# PWR.net
KiCad netlist of a schematic drawn in Altium Designer
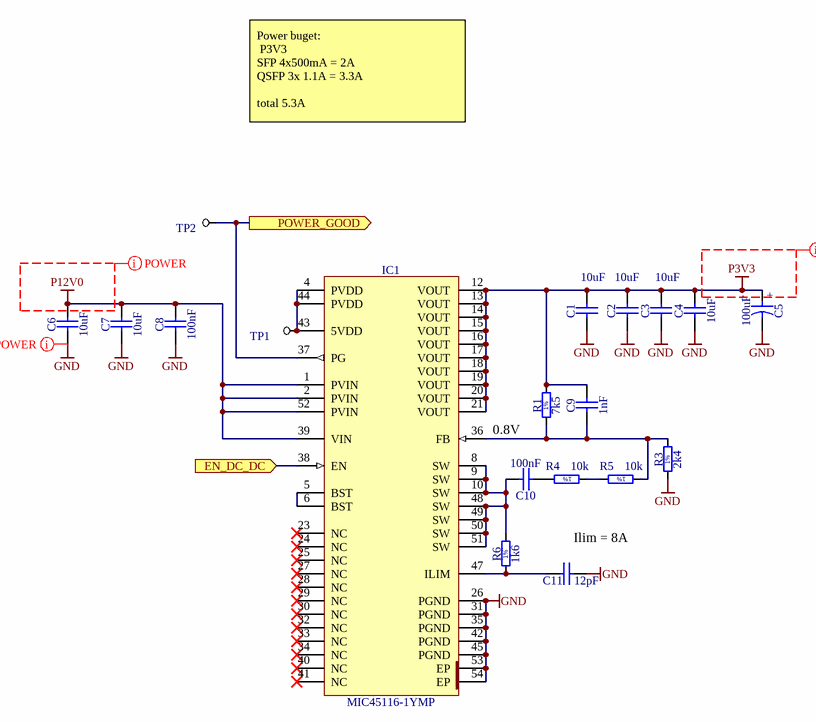
[diagram p0: PWR.SchDoc]

(export (version "E")
  (design (tool "Eeschema 10.0.6"))
  (components
    (comp (ref "C1")
      (value "10uF")
      (footprint "CAPC2012X135N")
      (description "Non-polarised capacitor")
      (fields
        (field (name "PART NUMBER") "CC0805_10UF_10V_10%_X7R")
        (field (name "VOLTAGE") "10V")
        (field (name "AUTHOR") "CERN DEM JLC")
      )
      (libsource (lib "Capacitors") (part "Capacitor - non polarized"))
    )
    (comp (ref "C2")
      (value "10uF")
      (footprint "CAPC2012X135N")
      (description "Non-polarised capacitor")
      (fields
        (field (name "PART NUMBER") "CC0805_10UF_10V_10%_X7R")
        (field (name "VOLTAGE") "10V")
        (field (name "AUTHOR") "CERN DEM JLC")
      )
      (libsource (lib "Capacitors") (part "Capacitor - non polarized"))
    )
    (comp (ref "C3")
      (value "10uF")
      (footprint "CAPC2012X135N")
      (description "Non-polarised capacitor")
      (fields
        (field (name "PART NUMBER") "CC0805_10UF_10V_10%_X7R")
        (field (name "VOLTAGE") "10V")
        (field (name "AUTHOR") "CERN DEM JLC")
      )
      (libsource (lib "Capacitors") (part "Capacitor - non polarized"))
    )
    (comp (ref "C4")
      (value "10uF")
      (footprint "CAPC2012X135N")
      (description "Non-polarised capacitor")
      (fields
        (field (name "PART NUMBER") "CC0805_10UF_10V_10%_X7R")
        (field (name "VOLTAGE") "10V")
        (field (name "AUTHOR") "CERN DEM JLC")
      )
      (libsource (lib "Capacitors") (part "Capacitor - non polarized"))
    )
    (comp (ref "C5")
      (value "100uF")
      (footprint "CAPAE660X540N")
      (description "Polarised capacitor")
      (fields
        (field (name "PART NUMBER") "CAE660-540_100UF_16V_20%")
        (field (name "VOLTAGE") "16V")
        (field (name "AUTHOR") "CERN DEM JLC")
      )
      (libsource (lib "Capacitors") (part "Capacitor - polarized"))
    )
    (comp (ref "C6")
      (value "10uF")
      (footprint "CAPC3216X140N")
      (description "Non-polarised capacitor")
      (fields
        (field (name "PART NUMBER") "CC1206_10UF_16V_10%_X7R")
        (field (name "VOLTAGE") "16V")
        (field (name "AUTHOR") "CERN DEM JLC")
      )
      (libsource (lib "Capacitors") (part "Capacitor - non polarized"))
    )
    (comp (ref "C7")
      (value "10uF")
      (footprint "CAPC3216X140N")
      (description "Non-polarised capacitor")
      (fields
        (field (name "PART NUMBER") "CC1206_10UF_16V_10%_X7R")
        (field (name "VOLTAGE") "16V")
        (field (name "AUTHOR") "CERN DEM JLC")
      )
      (libsource (lib "Capacitors") (part "Capacitor - non polarized"))
    )
    (comp (ref "C8")
      (value "100nF")
      (footprint "CAPC1005X55N")
      (description "Non-polarised capacitor")
      (fields
        (field (name "PART NUMBER") "CC0402_100NF_16V_10%_X5R")
        (field (name "VOLTAGE") "16V")
        (field (name "AUTHOR") "CERN DEM JLC")
      )
      (libsource (lib "Capacitors") (part "Capacitor - non polarized"))
    )
    (comp (ref "C9")
      (value "1nF")
      (footprint "CAPC1005X55N")
      (description "Non-polarised capacitor")
      (fields
        (field (name "PART NUMBER") "CC0402_1NF_50V_10%_X7R")
        (field (name "VOLTAGE") "50V")
        (field (name "AUTHOR") "CERN DEM JLC")
      )
      (libsource (lib "Capacitors") (part "Capacitor - non polarized"))
    )
    (comp (ref "C10")
      (value "100nF")
      (footprint "CAPC1005X55N")
      (description "Non-polarised capacitor")
      (fields
        (field (name "PART NUMBER") "CC0402_100NF_16V_10%_X5R")
        (field (name "VOLTAGE") "16V")
        (field (name "AUTHOR") "CERN DEM JLC")
      )
      (libsource (lib "Capacitors") (part "Capacitor - non polarized"))
    )
    (comp (ref "C11")
      (value "12pF")
      (footprint "CAPC1005X55N")
      (description "Non-polarised capacitor")
      (fields
        (field (name "PART NUMBER") "CC0402_12PF_50V_5%_C0G")
        (field (name "VOLTAGE") "50V")
        (field (name "AUTHOR") "CERN DEM JLC")
      )
      (libsource (lib "Capacitors") (part "Capacitor - non polarized"))
    )
    (comp (ref "IC1")
      (value "MIC45116-1YMP")
      (footprint "MICROCHIP_H3QFN88-52LD-PL-3")
      (description "0.8V to 85% PVIN (4.75-19V), 6A Synchronous Step-Down Regulator Module")
      (fields (field (name "MANUFACTURER") "MICROCHIP TECHNOLOGY") (field (name "AUTHOR") "CERN DEM JMW"))
      (libsource (lib "ICs And Semiconductors") (part "MIC45116"))
    )
    (comp (ref "R1")
      (value "7k5")
      (footprint "RESC1005X40N")
      (description "Resistor - 1%")
      (fields
        (field (name "PART NUMBER") "R0402_7K5_1%_0.0625W_100PPM")
        (field (name "POWER") "0.0625W")
        (field (name "AUTHOR") "CERN DEM JLC")
      )
      (libsource (lib "Resistors") (part "Resistor - 1%"))
    )
    (comp (ref "R3")
      (value "2k4")
      (footprint "RESC1005X40N")
      (description "Resistor - 1%")
      (fields
        (field (name "PART NUMBER") "R0402_2K4_1%_0.0625W_100PPM")
        (field (name "POWER") "0.0625W")
        (field (name "AUTHOR") "CERN DEM JLC")
      )
      (libsource (lib "Resistors") (part "Resistor - 1%"))
    )
    (comp (ref "R4")
      (value "10k")
      (footprint "RESC1005X40N")
      (description "Resistor - 1%")
      (fields
        (field (name "PART NUMBER") "R0402_10K_1%_0.0625W_100PPM")
        (field (name "POWER") "0.0625W")
        (field (name "AUTHOR") "CERN DEM JLC")
      )
      (libsource (lib "Resistors") (part "Resistor - 1%"))
    )
    (comp (ref "R5")
      (value "10k")
      (footprint "RESC1005X40N")
      (description "Resistor - 1%")
      (fields
        (field (name "PART NUMBER") "R0402_10K_1%_0.0625W_100PPM")
        (field (name "POWER") "0.0625W")
        (field (name "AUTHOR") "CERN DEM JLC")
      )
      (libsource (lib "Resistors") (part "Resistor - 1%"))
    )
    (comp (ref "R6")
      (value "1k6")
      (footprint "RESC1005X40N")
      (description "Resistor - 1%")
      (fields
        (field (name "PART NUMBER") "R0402_1K6_1%_0.0625W_100PPM")
        (field (name "POWER") "0.0625W")
        (field (name "AUTHOR") "CERN DEM JLC")
      )
      (libsource (lib "Resistors") (part "Resistor - 1%"))
    )
    (comp (ref "TP1")
      (value "TP")
      (footprint "TP")
      (description "Testpoint")
      (libsource (lib "LIBRARY_SCH") (part "TP"))
    )
    (comp (ref "TP2")
      (value "TP")
      (footprint "TP")
      (description "Testpoint")
      (libsource (lib "LIBRARY_SCH") (part "TP"))
    )
  )
  (nets
    (net (code "1") (name "/EN_DC_DC") (class "Default")
      (node (ref "IC1") (pin "38") (pinfunction "EN_38") (pintype "input"))
    )
    (net (code "2") (name "/POWER_GOOD") (class "Default")
      (node (ref "IC1") (pin "37") (pinfunction "PG_37") (pintype "output"))
      (node (ref "TP2") (pin "1") (pintype "passive"))
    )
    (net (code "3") (name "GND") (class "Default")
      (node (ref "C1") (pin "1") (pinfunction "1_1") (pintype "passive"))
      (node (ref "C11") (pin "1") (pinfunction "1_1") (pintype "passive"))
      (node (ref "C2") (pin "1") (pinfunction "1_1") (pintype "passive"))
      (node (ref "C3") (pin "1") (pinfunction "1_1") (pintype "passive"))
      (node (ref "C4") (pin "1") (pinfunction "1_1") (pintype "passive"))
      (node (ref "C5") (pin "2") (pinfunction "2_2") (pintype "passive"))
      (node (ref "C6") (pin "1") (pinfunction "1_1") (pintype "passive"))
      (node (ref "C7") (pin "1") (pinfunction "1_1") (pintype "passive"))
      (node (ref "C8") (pin "1") (pinfunction "1_1") (pintype "passive"))
      (node (ref "IC1") (pin "26") (pinfunction "PGND_26") (pintype "power_in"))
      (node (ref "IC1") (pin "31") (pinfunction "PGND_31") (pintype "power_in"))
      (node (ref "IC1") (pin "35") (pinfunction "PGND_35") (pintype "power_in"))
      (node (ref "IC1") (pin "42") (pinfunction "PGND_42") (pintype "power_in"))
      (node (ref "IC1") (pin "45") (pinfunction "PGND_45") (pintype "power_in"))
      (node (ref "IC1") (pin "53") (pinfunction "EP_53") (pintype "power_in"))
      (node (ref "IC1") (pin "54") (pinfunction "EP_54") (pintype "power_in"))
      (node (ref "R3") (pin "1") (pinfunction "1_1") (pintype "passive"))
    )
    (net (code "4") (name "Net-(C10-Pad1)") (class "Default")
      (node (ref "C10") (pin "1") (pinfunction "1_1") (pintype "passive"))
      (node (ref "R4") (pin "2") (pinfunction "2_2") (pintype "passive"))
    )
    (net (code "5") (name "Net-(C10-Pad2)") (class "Default")
      (node (ref "C10") (pin "2") (pinfunction "2_2") (pintype "passive"))
      (node (ref "IC1") (pin "10") (pinfunction "SW_10") (pintype "passive"))
      (node (ref "IC1") (pin "48") (pinfunction "SW_48") (pintype "passive"))
      (node (ref "IC1") (pin "49") (pinfunction "SW_49") (pintype "passive"))
      (node (ref "IC1") (pin "50") (pinfunction "SW_50") (pintype "passive"))
      (node (ref "IC1") (pin "51") (pinfunction "SW_51") (pintype "passive"))
      (node (ref "IC1") (pin "8") (pinfunction "SW_8") (pintype "passive"))
      (node (ref "IC1") (pin "9") (pinfunction "SW_9") (pintype "passive"))
      (node (ref "R6") (pin "2") (pinfunction "2_2") (pintype "passive"))
    )
    (net (code "6") (name "Net-(IC1-5VDD)") (class "Default")
      (node (ref "IC1") (pin "4") (pinfunction "PVDD_4") (pintype "power_in"))
      (node (ref "IC1") (pin "43") (pinfunction "5VDD_43") (pintype "power_in"))
      (node (ref "IC1") (pin "44") (pinfunction "PVDD_44") (pintype "power_in"))
      (node (ref "TP1") (pin "1") (pintype "passive"))
    )
    (net (code "7") (name "Net-(IC1-BST-Pad5)") (class "Default")
      (node (ref "IC1") (pin "5") (pinfunction "BST_5") (pintype "passive"))
      (node (ref "IC1") (pin "6") (pinfunction "BST_6") (pintype "passive"))
    )
    (net (code "8") (name "Net-(IC1-FB)") (class "Default")
      (node (ref "C9") (pin "1") (pinfunction "1_1") (pintype "passive"))
      (node (ref "IC1") (pin "36") (pinfunction "FB_36") (pintype "input"))
      (node (ref "R1") (pin "1") (pinfunction "1_1") (pintype "passive"))
      (node (ref "R3") (pin "2") (pinfunction "2_2") (pintype "passive"))
      (node (ref "R5") (pin "1") (pinfunction "1_1") (pintype "passive"))
    )
    (net (code "9") (name "Net-(IC1-ILIM)") (class "Default")
      (node (ref "C11") (pin "2") (pinfunction "2_2") (pintype "passive"))
      (node (ref "IC1") (pin "47") (pinfunction "ILIM_47") (pintype "passive"))
      (node (ref "R6") (pin "1") (pinfunction "1_1") (pintype "passive"))
    )
    (net (code "10") (name "Net-(R4-Pad1)") (class "Default")
      (node (ref "R4") (pin "1") (pinfunction "1_1") (pintype "passive"))
      (node (ref "R5") (pin "2") (pinfunction "2_2") (pintype "passive"))
    )
    (net (code "11") (name "P3V3") (class "Default")
      (node (ref "C1") (pin "2") (pinfunction "2_2") (pintype "passive"))
      (node (ref "C2") (pin "2") (pinfunction "2_2") (pintype "passive"))
      (node (ref "C3") (pin "2") (pinfunction "2_2") (pintype "passive"))
      (node (ref "C4") (pin "2") (pinfunction "2_2") (pintype "passive"))
      (node (ref "C5") (pin "1") (pinfunction "1_1") (pintype "passive"))
      (node (ref "C9") (pin "2") (pinfunction "2_2") (pintype "passive"))
      (node (ref "IC1") (pin "12") (pinfunction "VOUT_12") (pintype "power_in"))
      (node (ref "IC1") (pin "13") (pinfunction "VOUT_13") (pintype "power_in"))
      (node (ref "IC1") (pin "14") (pinfunction "VOUT_14") (pintype "power_in"))
      (node (ref "IC1") (pin "15") (pinfunction "VOUT_15") (pintype "power_in"))
      (node (ref "IC1") (pin "16") (pinfunction "VOUT_16") (pintype "power_in"))
      (node (ref "IC1") (pin "17") (pinfunction "VOUT_17") (pintype "power_in"))
      (node (ref "IC1") (pin "18") (pinfunction "VOUT_18") (pintype "power_in"))
      (node (ref "IC1") (pin "19") (pinfunction "VOUT_19") (pintype "power_in"))
      (node (ref "IC1") (pin "20") (pinfunction "VOUT_20") (pintype "power_in"))
      (node (ref "IC1") (pin "21") (pinfunction "VOUT_21") (pintype "power_in"))
      (node (ref "R1") (pin "2") (pinfunction "2_2") (pintype "passive"))
    )
    (net (code "12") (name "P12V0") (class "Default")
      (node (ref "C6") (pin "2") (pinfunction "2_2") (pintype "passive"))
      (node (ref "C7") (pin "2") (pinfunction "2_2") (pintype "passive"))
      (node (ref "C8") (pin "2") (pinfunction "2_2") (pintype "passive"))
      (node (ref "IC1") (pin "1") (pinfunction "PVIN_1") (pintype "power_in"))
      (node (ref "IC1") (pin "2") (pinfunction "PVIN_2") (pintype "power_in"))
      (node (ref "IC1") (pin "39") (pinfunction "VIN_39") (pintype "power_in"))
      (node (ref "IC1") (pin "52") (pinfunction "PVIN_52") (pintype "power_in"))
    )
    (net (code "13") (name "unconnected-(IC1-NC-Pad23)") (class "Default")
      (node (ref "IC1") (pin "23") (pinfunction "NC_23") (pintype "passive+no_connect"))
    )
    (net (code "14") (name "unconnected-(IC1-NC-Pad24)") (class "Default")
      (node (ref "IC1") (pin "24") (pinfunction "NC_24") (pintype "passive+no_connect"))
    )
    (net (code "15") (name "unconnected-(IC1-NC-Pad25)") (class "Default")
      (node (ref "IC1") (pin "25") (pinfunction "NC_25") (pintype "passive+no_connect"))
    )
    (net (code "16") (name "unconnected-(IC1-NC-Pad27)") (class "Default")
      (node (ref "IC1") (pin "27") (pinfunction "NC_27") (pintype "passive+no_connect"))
    )
    (net (code "17") (name "unconnected-(IC1-NC-Pad28)") (class "Default")
      (node (ref "IC1") (pin "28") (pinfunction "NC_28") (pintype "passive+no_connect"))
    )
    (net (code "18") (name "unconnected-(IC1-NC-Pad29)") (class "Default")
      (node (ref "IC1") (pin "29") (pinfunction "NC_29") (pintype "passive+no_connect"))
    )
    (net (code "19") (name "unconnected-(IC1-NC-Pad30)") (class "Default")
      (node (ref "IC1") (pin "30") (pinfunction "NC_30") (pintype "passive+no_connect"))
    )
    (net (code "20") (name "unconnected-(IC1-NC-Pad32)") (class "Default")
      (node (ref "IC1") (pin "32") (pinfunction "NC_32") (pintype "passive+no_connect"))
    )
    (net (code "21") (name "unconnected-(IC1-NC-Pad33)") (class "Default")
      (node (ref "IC1") (pin "33") (pinfunction "NC_33") (pintype "passive+no_connect"))
    )
    (net (code "22") (name "unconnected-(IC1-NC-Pad34)") (class "Default")
      (node (ref "IC1") (pin "34") (pinfunction "NC_34") (pintype "passive+no_connect"))
    )
    (net (code "23") (name "unconnected-(IC1-NC-Pad40)") (class "Default")
      (node (ref "IC1") (pin "40") (pinfunction "NC_40") (pintype "passive+no_connect"))
    )
    (net (code "24") (name "unconnected-(IC1-NC-Pad41)") (class "Default")
      (node (ref "IC1") (pin "41") (pinfunction "NC_41") (pintype "passive+no_connect"))
    )
  )
)
